# stuffMonitor.net
KiCad netlist of a schematic drawn in EAGLE
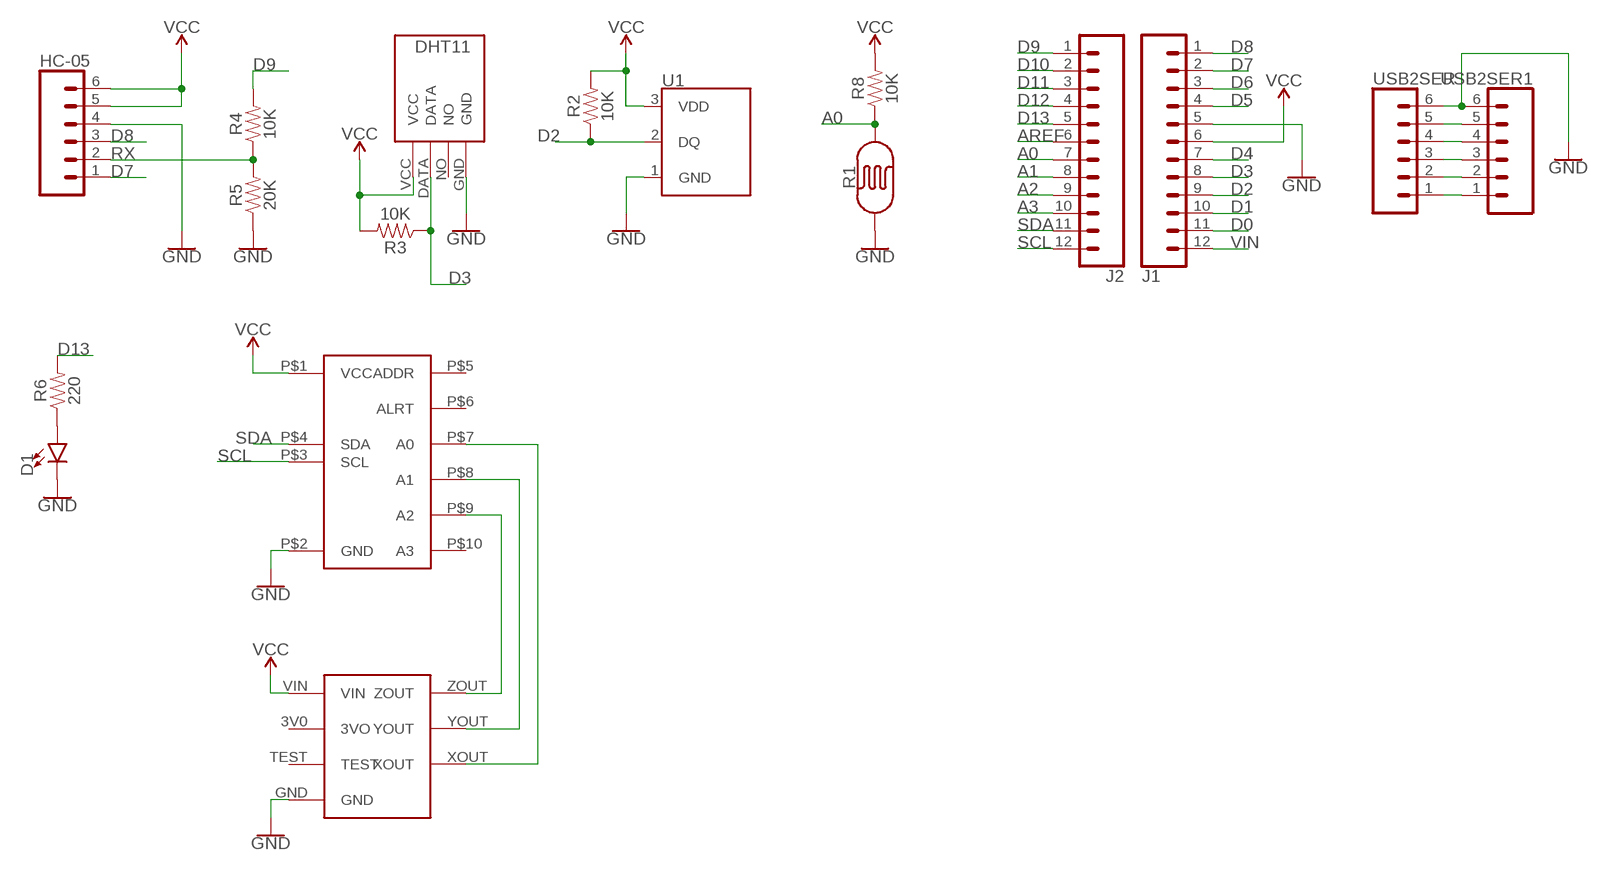
[diagram p0: schematic, sheet 1]

(export (version "E")
  (design (tool "Eeschema 10.0.6"))
  (components
    (comp (ref "D1")
      (value "LED5MM")
      (footprint "eagle-import:LED_5MM")
      (libsource (lib "eagle-import") (part "LED5MM"))
    )
    (comp (ref "HC-05")
      (value "CONN_06NO_SILK_FEMALE_PTH")
      (footprint "eagle-import:1X06_NO_SILK")
      (libsource (lib "eagle-import") (part "CONN_06NO_SILK_FEMALE_PTH"))
    )
    (comp (ref "J1")
      (value "CONN_12")
      (footprint "eagle-import:1X12")
      (libsource (lib "eagle-import") (part "CONN_12"))
    )
    (comp (ref "J2")
      (value "CONN_12")
      (footprint "eagle-import:1X12")
      (libsource (lib "eagle-import") (part "CONN_12"))
    )
    (comp (ref "R1")
      (value "PHOTOCELLPTH")
      (footprint "eagle-import:PHOTOCELL")
      (libsource (lib "eagle-import") (part "PHOTOCELLPTH"))
    )
    (comp (ref "R2")
      (value "10K")
      (footprint "eagle-import:AXIAL-0.1")
      (libsource (lib "eagle-import") (part "1KOHM-VERT-1/4W-5%"))
    )
    (comp (ref "R3")
      (value "10K")
      (footprint "eagle-import:AXIAL-0.1")
      (libsource (lib "eagle-import") (part "1KOHM-VERT-1/4W-5%"))
    )
    (comp (ref "R4")
      (value "10K")
      (footprint "eagle-import:AXIAL-0.1")
      (libsource (lib "eagle-import") (part "1KOHM-VERT-1/4W-5%"))
    )
    (comp (ref "R5")
      (value "20K")
      (footprint "eagle-import:AXIAL-0.1")
      (libsource (lib "eagle-import") (part "1KOHM-VERT-1/4W-5%"))
    )
    (comp (ref "R6")
      (value "220")
      (footprint "eagle-import:AXIAL-0.1")
      (libsource (lib "eagle-import") (part "1KOHM-VERT-1/4W-5%"))
    )
    (comp (ref "R8")
      (value "10K")
      (footprint "eagle-import:AXIAL-0.1")
      (libsource (lib "eagle-import") (part "1KOHM-VERT-1/4W-5%"))
    )
    (comp (ref "U$2")
      (value "SCRAPACCEL")
      (footprint "eagle-import:SCRAPACCELANALOG")
      (libsource (lib "eagle-import") (part "SCRAPACCEL"))
    )
    (comp (ref "U$3")
      (value "12BITADCADAFRUIT")
      (footprint "eagle-import:ADC12BITADAFRUIT")
      (libsource (lib "eagle-import") (part "12BITADCADAFRUIT"))
    )
    (comp (ref "U$4")
      (value "DHT11-PION.")
      (footprint "eagle-import:DHT11-PION.")
      (libsource (lib "eagle-import") (part "DHT11-PION."))
    )
    (comp (ref "U1")
      (value "DS18B20")
      (footprint "eagle-import:TO-92-AMMO")
      (libsource (lib "eagle-import") (part "DS18B20"))
    )
    (comp (ref "USB2SER")
      (value "CONN_06NO_SILK_FEMALE_PTH")
      (footprint "eagle-import:1X06_NO_SILK")
      (libsource (lib "eagle-import") (part "CONN_06NO_SILK_FEMALE_PTH"))
    )
    (comp (ref "USB2SER1")
      (value "CONN_06NO_SILK_FEMALE_PTH")
      (footprint "eagle-import:1X06_NO_SILK")
      (libsource (lib "eagle-import") (part "CONN_06NO_SILK_FEMALE_PTH"))
    )
  )
  (nets
    (net (code "1") (name "/A0") (class "Default")
      (node (ref "J2") (pin "7") (pinfunction "7_7") (pintype "passive"))
      (node (ref "R1") (pin "2") (pinfunction "P$2_2") (pintype "bidirectional"))
      (node (ref "R8") (pin "P$1") (pinfunction "1_P$1") (pintype "passive"))
    )
    (net (code "2") (name "/A1") (class "Default")
      (node (ref "J2") (pin "8") (pinfunction "8_8") (pintype "passive"))
    )
    (net (code "3") (name "/A2") (class "Default")
      (node (ref "J2") (pin "9") (pinfunction "9_9") (pintype "passive"))
    )
    (net (code "4") (name "/A3") (class "Default")
      (node (ref "J2") (pin "10") (pinfunction "10_10") (pintype "passive"))
    )
    (net (code "5") (name "/AREF") (class "Default")
      (node (ref "J2") (pin "6") (pinfunction "6_6") (pintype "passive"))
    )
    (net (code "6") (name "/D0") (class "Default")
      (node (ref "J1") (pin "11") (pinfunction "11_11") (pintype "passive"))
    )
    (net (code "7") (name "/D1") (class "Default")
      (node (ref "J1") (pin "10") (pinfunction "10_10") (pintype "passive"))
    )
    (net (code "8") (name "/D2") (class "Default")
      (node (ref "J1") (pin "9") (pinfunction "9_9") (pintype "passive"))
      (node (ref "R2") (pin "P$1") (pinfunction "1_P$1") (pintype "passive"))
      (node (ref "U1") (pin "2") (pinfunction "DQ_2") (pintype "bidirectional"))
    )
    (net (code "9") (name "/D3") (class "Default")
      (node (ref "J1") (pin "8") (pinfunction "8_8") (pintype "passive"))
      (node (ref "R3") (pin "P$1") (pinfunction "1_P$1") (pintype "passive"))
      (node (ref "U$4") (pin "DATA") (pinfunction "DATA_DATA") (pintype "bidirectional"))
    )
    (net (code "10") (name "/D4") (class "Default")
      (node (ref "J1") (pin "7") (pinfunction "7_7") (pintype "passive"))
    )
    (net (code "11") (name "/D5") (class "Default")
      (node (ref "J1") (pin "4") (pinfunction "4_4") (pintype "passive"))
    )
    (net (code "12") (name "/D6") (class "Default")
      (node (ref "J1") (pin "3") (pinfunction "3_3") (pintype "passive"))
    )
    (net (code "13") (name "/D7") (class "Default")
      (node (ref "HC-05") (pin "1") (pinfunction "1_1") (pintype "passive"))
      (node (ref "J1") (pin "2") (pinfunction "2_2") (pintype "passive"))
    )
    (net (code "14") (name "/D8") (class "Default")
      (node (ref "HC-05") (pin "3") (pinfunction "3_3") (pintype "passive"))
      (node (ref "J1") (pin "1") (pinfunction "1_1") (pintype "passive"))
    )
    (net (code "15") (name "/D9") (class "Default")
      (node (ref "J2") (pin "1") (pinfunction "1_1") (pintype "passive"))
      (node (ref "R4") (pin "P$2") (pinfunction "2_P$2") (pintype "passive"))
    )
    (net (code "16") (name "/D10") (class "Default")
      (node (ref "J2") (pin "2") (pinfunction "2_2") (pintype "passive"))
    )
    (net (code "17") (name "/D11") (class "Default")
      (node (ref "J2") (pin "3") (pinfunction "3_3") (pintype "passive"))
    )
    (net (code "18") (name "/D12") (class "Default")
      (node (ref "J2") (pin "4") (pinfunction "4_4") (pintype "passive"))
    )
    (net (code "19") (name "/D13") (class "Default")
      (node (ref "J2") (pin "5") (pinfunction "5_5") (pintype "passive"))
      (node (ref "R6") (pin "P$2") (pinfunction "2_P$2") (pintype "passive"))
    )
    (net (code "20") (name "/RX") (class "Default")
      (node (ref "HC-05") (pin "2") (pinfunction "2_2") (pintype "passive"))
      (node (ref "R4") (pin "P$1") (pinfunction "1_P$1") (pintype "passive"))
      (node (ref "R5") (pin "P$2") (pinfunction "2_P$2") (pintype "passive"))
    )
    (net (code "21") (name "/SCL") (class "Default")
      (node (ref "J2") (pin "12") (pinfunction "12_12") (pintype "passive"))
      (node (ref "U$3") (pin "P$3") (pinfunction "SCL_P$3") (pintype "bidirectional"))
    )
    (net (code "22") (name "/SDA") (class "Default")
      (node (ref "J2") (pin "11") (pinfunction "11_11") (pintype "passive"))
      (node (ref "U$3") (pin "P$4") (pinfunction "SDA_P$4") (pintype "bidirectional"))
    )
    (net (code "23") (name "/VIN") (class "Default")
      (node (ref "J1") (pin "12") (pinfunction "12_12") (pintype "passive"))
    )
    (net (code "24") (name "GND") (class "Default")
      (node (ref "D1") (pin "K") (pinfunction "C_K") (pintype "passive"))
      (node (ref "HC-05") (pin "4") (pinfunction "4_4") (pintype "passive"))
      (node (ref "J1") (pin "5") (pinfunction "5_5") (pintype "passive"))
      (node (ref "R1") (pin "1") (pinfunction "P$1_1") (pintype "bidirectional"))
      (node (ref "R5") (pin "P$1") (pinfunction "1_P$1") (pintype "passive"))
      (node (ref "U$2") (pin "GND") (pinfunction "GND_GND") (pintype "bidirectional"))
      (node (ref "U$3") (pin "P$2") (pinfunction "GND_P$2") (pintype "bidirectional"))
      (node (ref "U$4") (pin "GND") (pinfunction "GND_GND") (pintype "bidirectional"))
      (node (ref "U1") (pin "1") (pinfunction "GND_1") (pintype "power_in"))
      (node (ref "USB2SER") (pin "6") (pinfunction "6_6") (pintype "passive"))
      (node (ref "USB2SER1") (pin "6") (pinfunction "6_6") (pintype "passive"))
    )
    (net (code "25") (name "Net-(R6-1)") (class "Default")
      (node (ref "D1") (pin "A") (pinfunction "A_A") (pintype "passive"))
      (node (ref "R6") (pin "P$1") (pinfunction "1_P$1") (pintype "passive"))
    )
    (net (code "26") (name "Net-(U$3-A0)") (class "Default")
      (node (ref "U$2") (pin "XOUT") (pinfunction "XOUT_XOUT") (pintype "bidirectional"))
      (node (ref "U$3") (pin "P$7") (pinfunction "A0_P$7") (pintype "bidirectional"))
    )
    (net (code "27") (name "Net-(U$3-A1)") (class "Default")
      (node (ref "U$2") (pin "YOUT") (pinfunction "YOUT_YOUT") (pintype "bidirectional"))
      (node (ref "U$3") (pin "P$8") (pinfunction "A1_P$8") (pintype "bidirectional"))
    )
    (net (code "28") (name "Net-(U$3-A2)") (class "Default")
      (node (ref "U$2") (pin "ZOUT") (pinfunction "ZOUT_ZOUT") (pintype "bidirectional"))
      (node (ref "U$3") (pin "P$9") (pinfunction "A2_P$9") (pintype "bidirectional"))
    )
    (net (code "29") (name "Net-(USB2SER-Pad1)") (class "Default")
      (node (ref "USB2SER") (pin "1") (pinfunction "1_1") (pintype "passive"))
      (node (ref "USB2SER1") (pin "1") (pinfunction "1_1") (pintype "passive"))
    )
    (net (code "30") (name "Net-(USB2SER-Pad2)") (class "Default")
      (node (ref "USB2SER") (pin "2") (pinfunction "2_2") (pintype "passive"))
      (node (ref "USB2SER1") (pin "2") (pinfunction "2_2") (pintype "passive"))
    )
    (net (code "31") (name "Net-(USB2SER-Pad3)") (class "Default")
      (node (ref "USB2SER") (pin "3") (pinfunction "3_3") (pintype "passive"))
      (node (ref "USB2SER1") (pin "3") (pinfunction "3_3") (pintype "passive"))
    )
    (net (code "32") (name "Net-(USB2SER-Pad4)") (class "Default")
      (node (ref "USB2SER") (pin "4") (pinfunction "4_4") (pintype "passive"))
      (node (ref "USB2SER1") (pin "4") (pinfunction "4_4") (pintype "passive"))
    )
    (net (code "33") (name "Net-(USB2SER-Pad5)") (class "Default")
      (node (ref "USB2SER") (pin "5") (pinfunction "5_5") (pintype "passive"))
      (node (ref "USB2SER1") (pin "5") (pinfunction "5_5") (pintype "passive"))
    )
    (net (code "34") (name "VCC") (class "Default")
      (node (ref "HC-05") (pin "5") (pinfunction "5_5") (pintype "passive"))
      (node (ref "HC-05") (pin "6") (pinfunction "6_6") (pintype "passive"))
      (node (ref "J1") (pin "6") (pinfunction "6_6") (pintype "passive"))
      (node (ref "R2") (pin "P$2") (pinfunction "2_P$2") (pintype "passive"))
      (node (ref "R3") (pin "P$2") (pinfunction "2_P$2") (pintype "passive"))
      (node (ref "R8") (pin "P$2") (pinfunction "2_P$2") (pintype "passive"))
      (node (ref "U$2") (pin "VIN") (pinfunction "VIN_VIN") (pintype "bidirectional"))
      (node (ref "U$3") (pin "P$1") (pinfunction "VCC_P$1") (pintype "bidirectional"))
      (node (ref "U$4") (pin "VCC") (pinfunction "VCC_VCC") (pintype "bidirectional"))
      (node (ref "U1") (pin "3") (pinfunction "VDD_3") (pintype "power_in"))
    )
    (net (code "35") (name "unconnected-(U$2-3VO-Pad3V0)") (class "Default")
      (node (ref "U$2") (pin "3V0") (pinfunction "3VO_3V0") (pintype "bidirectional"))
    )
    (net (code "36") (name "unconnected-(U$2-PadTEST)") (class "Default")
      (node (ref "U$2") (pin "TEST") (pinfunction "TEST_TEST") (pintype "bidirectional"))
    )
    (net (code "37") (name "unconnected-(U$3-A3-PadP$10)") (class "Default")
      (node (ref "U$3") (pin "P$10") (pinfunction "A3_P$10") (pintype "bidirectional"))
    )
    (net (code "38") (name "unconnected-(U$3-ADDR-PadP$5)") (class "Default")
      (node (ref "U$3") (pin "P$5") (pinfunction "ADDR_P$5") (pintype "bidirectional"))
    )
    (net (code "39") (name "unconnected-(U$3-ALRT-PadP$6)") (class "Default")
      (node (ref "U$3") (pin "P$6") (pinfunction "ALRT_P$6") (pintype "bidirectional"))
    )
    (net (code "40") (name "unconnected-(U$4-PadNO)") (class "Default")
      (node (ref "U$4") (pin "NO") (pinfunction "NO_NO") (pintype "bidirectional"))
    )
  )
)
